# Dispositivo_H2O_Esquem_tico.net
KiCad netlist of a schematic drawn in EasyEDA
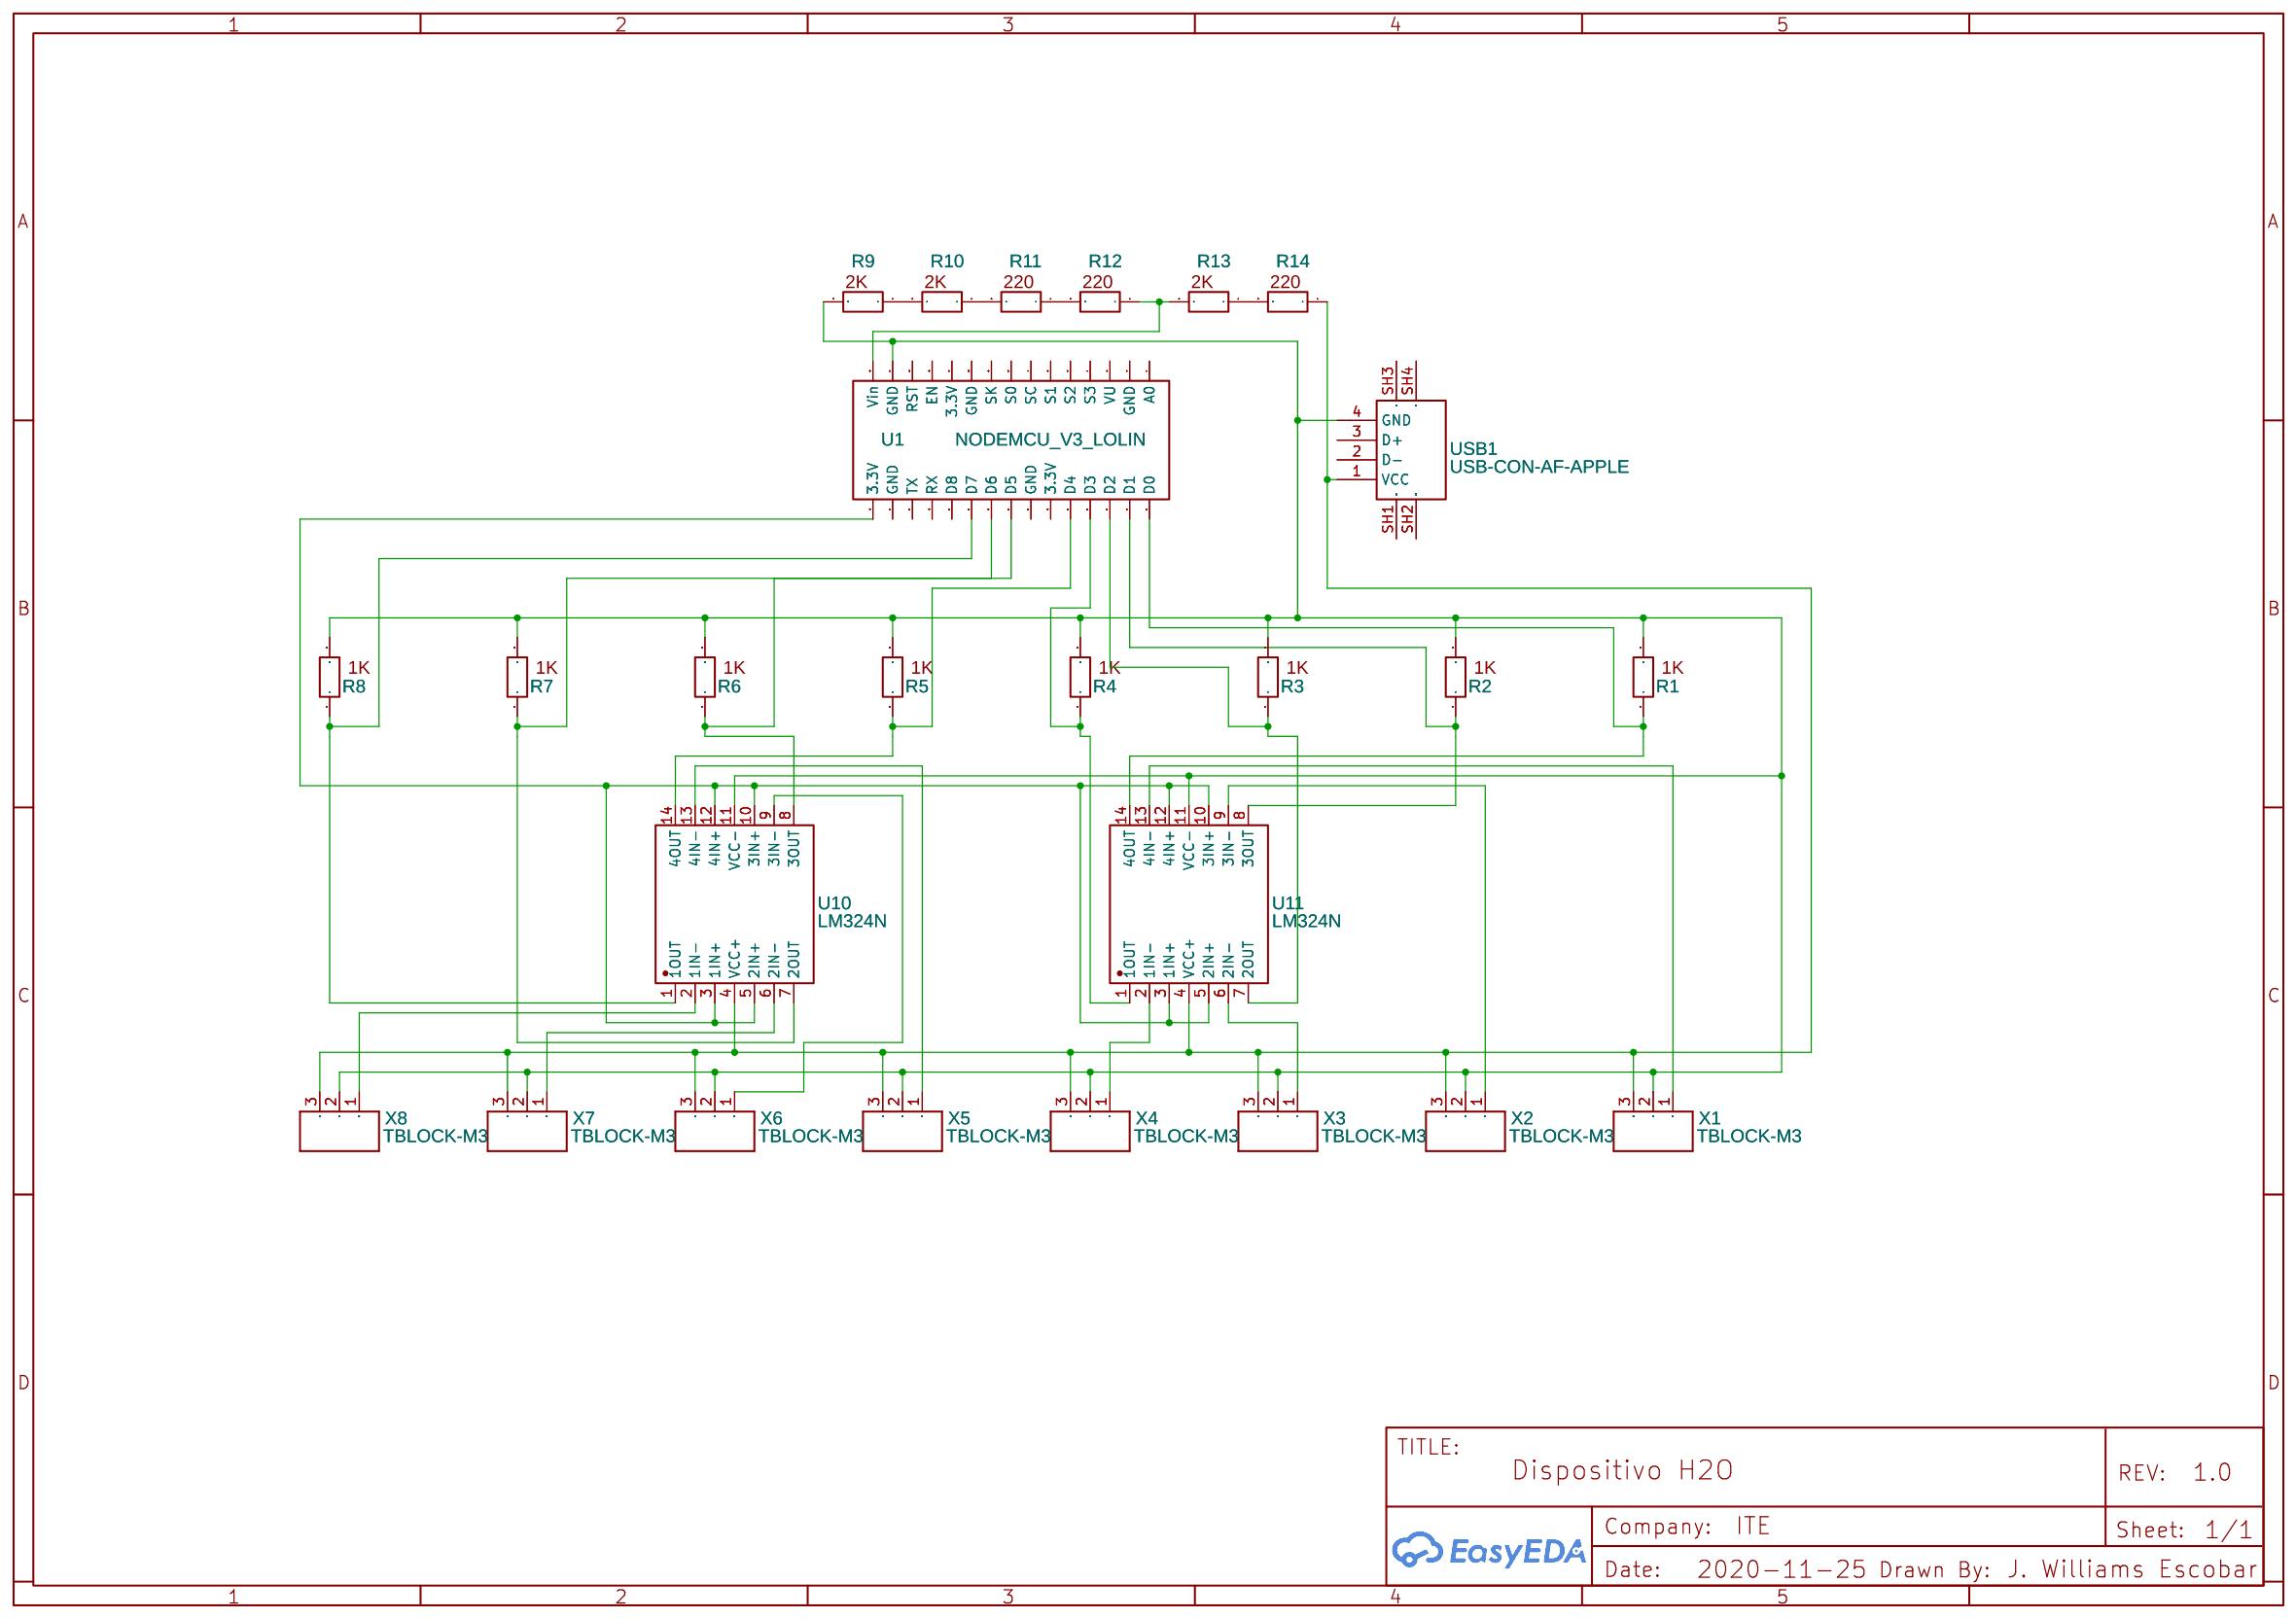
[diagram p0: schematic sheet]

(export (version "E")
  (design (tool "Eeschema 10.0.6"))
  (components
    (comp (ref "R1") (value "R9") (libsource (lib "") (part "Resistencia 1K_1")))
    (comp (ref "R2") (value "R9") (libsource (lib "") (part "Resistencia 1K_1")))
    (comp (ref "R3") (value "R9") (libsource (lib "") (part "Resistencia 1K_1")))
    (comp (ref "R4") (value "R9") (libsource (lib "") (part "Resistencia 1K_1")))
    (comp (ref "R5") (value "R9") (libsource (lib "") (part "Resistencia 1K_1")))
    (comp (ref "R6") (value "R9") (libsource (lib "") (part "Resistencia 1K_1")))
    (comp (ref "R7") (value "R9") (libsource (lib "") (part "Resistencia 1K_1")))
    (comp (ref "R8") (value "R9") (libsource (lib "") (part "Resistencia 1K_1")))
    (comp (ref "R9") (value "R9") (libsource (lib "") (part "Resistencia 1K_2")))
    (comp (ref "R10") (value "R16") (libsource (lib "") (part "Resistencia 1K_2")))
    (comp (ref "R11") (value "R17") (libsource (lib "") (part "Resistencia 1K")))
    (comp (ref "R12") (value "R9") (libsource (lib "") (part "Resistencia 1K")))
    (comp (ref "R13") (value "R9") (libsource (lib "") (part "Resistencia 1K_2")))
    (comp (ref "R14") (value "R9") (libsource (lib "") (part "Resistencia 1K")))
    (comp (ref "U1")
      (value "NODEMCU_V3_LOLIN")
      (fields (field (name "BOM_Manufacturer Part") "NodeMcu V3 LoLin"))
      (libsource (lib "") (part "NODEMCU_V3_LOLIN"))
    )
    (comp (ref "U10")
      (value "LM324N")
      (fields (field (name "BOM_Supplier Part") "C114380"))
      (libsource (lib "") (part "LM324N"))
    )
    (comp (ref "U11")
      (value "LM324N")
      (fields (field (name "BOM_Supplier Part") "C114380"))
      (libsource (lib "") (part "LM324N"))
    )
    (comp (ref "USB1")
      (value "USB-CON-AF-APPLE")
      (fields (field (name "BOM_Supplier Part") "C42567"))
      (libsource (lib "") (part "USB-CON-AF-APPLE"))
    )
    (comp (ref "X1") (value "TBLOCK-M3") (libsource (lib "") (part "TBLOCK-M3")))
    (comp (ref "X2") (value "TBLOCK-M3") (libsource (lib "") (part "TBLOCK-M3")))
    (comp (ref "X3") (value "TBLOCK-M3") (libsource (lib "") (part "TBLOCK-M3")))
    (comp (ref "X4") (value "TBLOCK-M3") (libsource (lib "") (part "TBLOCK-M3")))
    (comp (ref "X5") (value "TBLOCK-M3") (libsource (lib "") (part "TBLOCK-M3")))
    (comp (ref "X6") (value "TBLOCK-M3") (libsource (lib "") (part "TBLOCK-M3")))
    (comp (ref "X7") (value "TBLOCK-M3") (libsource (lib "") (part "TBLOCK-M3")))
    (comp (ref "X8") (value "TBLOCK-M3") (libsource (lib "") (part "TBLOCK-M3")))
  )
  (nets
    (net (code "1") (name "Net-(R10-Pad1)") (class "Default")
      (node (ref "R10") (pin "1") (pinfunction "1_1") (pintype "unspecified"))
      (node (ref "R11") (pin "2") (pinfunction "2_2") (pintype "unspecified"))
    )
    (net (code "2") (name "Net-(R10-Pad2)") (class "Default")
      (node (ref "R10") (pin "2") (pinfunction "2_2") (pintype "unspecified"))
      (node (ref "R9") (pin "1") (pinfunction "1_1") (pintype "unspecified"))
    )
    (net (code "3") (name "Net-(R11-Pad1)") (class "Default")
      (node (ref "R11") (pin "1") (pinfunction "1_1") (pintype "unspecified"))
      (node (ref "R12") (pin "2") (pinfunction "2_2") (pintype "unspecified"))
    )
    (net (code "4") (name "Net-(R13-Pad1)") (class "Default")
      (node (ref "R13") (pin "1") (pinfunction "1_1") (pintype "unspecified"))
      (node (ref "R14") (pin "2") (pinfunction "2_2") (pintype "unspecified"))
    )
    (net (code "5") (name "Net-(U1-D0)") (class "Default")
      (node (ref "R1") (pin "1") (pinfunction "1_1") (pintype "unspecified"))
      (node (ref "U1") (pin "30") (pinfunction "D0_30") (pintype "unspecified"))
      (node (ref "U11") (pin "14") (pinfunction "4OUT_14") (pintype "unspecified"))
    )
    (net (code "6") (name "Net-(U1-D1)") (class "Default")
      (node (ref "R2") (pin "1") (pinfunction "1_1") (pintype "unspecified"))
      (node (ref "U1") (pin "29") (pinfunction "D1_29") (pintype "unspecified"))
      (node (ref "U11") (pin "8") (pinfunction "3OUT_8") (pintype "unspecified"))
    )
    (net (code "7") (name "Net-(U1-D2)") (class "Default")
      (node (ref "R3") (pin "1") (pinfunction "1_1") (pintype "unspecified"))
      (node (ref "U1") (pin "28") (pinfunction "D2_28") (pintype "unspecified"))
      (node (ref "U11") (pin "7") (pinfunction "2OUT_7") (pintype "unspecified"))
    )
    (net (code "8") (name "Net-(U1-D3)") (class "Default")
      (node (ref "R4") (pin "1") (pinfunction "1_1") (pintype "unspecified"))
      (node (ref "U1") (pin "27") (pinfunction "D3_27") (pintype "unspecified"))
      (node (ref "U11") (pin "1") (pinfunction "1OUT_1") (pintype "unspecified"))
    )
    (net (code "9") (name "Net-(U1-D4)") (class "Default")
      (node (ref "R5") (pin "1") (pinfunction "1_1") (pintype "unspecified"))
      (node (ref "U1") (pin "26") (pinfunction "D4_26") (pintype "unspecified"))
      (node (ref "U10") (pin "14") (pinfunction "4OUT_14") (pintype "unspecified"))
    )
    (net (code "10") (name "Net-(U1-D5)") (class "Default")
      (node (ref "R6") (pin "1") (pinfunction "1_1") (pintype "unspecified"))
      (node (ref "U1") (pin "23") (pinfunction "D5_23") (pintype "unspecified"))
      (node (ref "U10") (pin "8") (pinfunction "3OUT_8") (pintype "unspecified"))
    )
    (net (code "11") (name "Net-(U1-D6)") (class "Default")
      (node (ref "R7") (pin "1") (pinfunction "1_1") (pintype "unspecified"))
      (node (ref "U1") (pin "22") (pinfunction "D6_22") (pintype "unspecified"))
      (node (ref "U10") (pin "7") (pinfunction "2OUT_7") (pintype "unspecified"))
    )
    (net (code "12") (name "Net-(U1-D7)") (class "Default")
      (node (ref "R8") (pin "1") (pinfunction "1_1") (pintype "unspecified"))
      (node (ref "U1") (pin "21") (pinfunction "D7_21") (pintype "unspecified"))
      (node (ref "U10") (pin "1") (pinfunction "1OUT_1") (pintype "unspecified"))
    )
    (net (code "13") (name "Net-(U1-Vin)") (class "Default")
      (node (ref "R12") (pin "1") (pinfunction "1_1") (pintype "unspecified"))
      (node (ref "R13") (pin "2") (pinfunction "2_2") (pintype "unspecified"))
      (node (ref "U1") (pin "15") (pinfunction "Vin_15") (pintype "unspecified"))
    )
    (net (code "14") (name "Net-(U10-1IN+)") (class "Default")
      (node (ref "U1") (pin "16") (pinfunction "3.3V_16") (pintype "unspecified"))
      (node (ref "U10") (pin "10") (pinfunction "3IN+_10") (pintype "unspecified"))
      (node (ref "U10") (pin "12") (pinfunction "4IN+_12") (pintype "unspecified"))
      (node (ref "U10") (pin "3") (pinfunction "1IN+_3") (pintype "unspecified"))
      (node (ref "U10") (pin "5") (pinfunction "2IN+_5") (pintype "unspecified"))
      (node (ref "U11") (pin "10") (pinfunction "3IN+_10") (pintype "unspecified"))
      (node (ref "U11") (pin "12") (pinfunction "4IN+_12") (pintype "unspecified"))
      (node (ref "U11") (pin "3") (pinfunction "1IN+_3") (pintype "unspecified"))
      (node (ref "U11") (pin "5") (pinfunction "2IN+_5") (pintype "unspecified"))
    )
    (net (code "15") (name "Net-(U10-1IN-)") (class "Default")
      (node (ref "U10") (pin "2") (pinfunction "1IN-_2") (pintype "unspecified"))
      (node (ref "X8") (pin "1") (pinfunction "P$1_1") (pintype "bidirectional"))
    )
    (net (code "16") (name "Net-(U10-2IN-)") (class "Default")
      (node (ref "U10") (pin "6") (pinfunction "2IN-_6") (pintype "unspecified"))
      (node (ref "X7") (pin "1") (pinfunction "P$1_1") (pintype "bidirectional"))
    )
    (net (code "17") (name "Net-(U10-3IN-)") (class "Default")
      (node (ref "U10") (pin "9") (pinfunction "3IN-_9") (pintype "unspecified"))
      (node (ref "X6") (pin "1") (pinfunction "P$1_1") (pintype "bidirectional"))
    )
    (net (code "18") (name "Net-(U10-4IN-)") (class "Default")
      (node (ref "U10") (pin "13") (pinfunction "4IN-_13") (pintype "unspecified"))
      (node (ref "X5") (pin "1") (pinfunction "P$1_1") (pintype "bidirectional"))
    )
    (net (code "19") (name "Net-(U10-VCC+)") (class "Default")
      (node (ref "R14") (pin "1") (pinfunction "1_1") (pintype "unspecified"))
      (node (ref "U10") (pin "4") (pinfunction "VCC+_4") (pintype "unspecified"))
      (node (ref "U11") (pin "4") (pinfunction "VCC+_4") (pintype "unspecified"))
      (node (ref "USB1") (pin "1") (pinfunction "VCC_1") (pintype "input"))
      (node (ref "X1") (pin "3") (pinfunction "P$3_3") (pintype "bidirectional"))
      (node (ref "X2") (pin "3") (pinfunction "P$3_3") (pintype "bidirectional"))
      (node (ref "X3") (pin "3") (pinfunction "P$3_3") (pintype "bidirectional"))
      (node (ref "X4") (pin "3") (pinfunction "P$3_3") (pintype "bidirectional"))
      (node (ref "X5") (pin "3") (pinfunction "P$3_3") (pintype "bidirectional"))
      (node (ref "X6") (pin "3") (pinfunction "P$3_3") (pintype "bidirectional"))
      (node (ref "X7") (pin "3") (pinfunction "P$3_3") (pintype "bidirectional"))
      (node (ref "X8") (pin "3") (pinfunction "P$3_3") (pintype "bidirectional"))
    )
    (net (code "20") (name "Net-(U10-VCC-)") (class "Default")
      (node (ref "R1") (pin "2") (pinfunction "2_2") (pintype "unspecified"))
      (node (ref "R2") (pin "2") (pinfunction "2_2") (pintype "unspecified"))
      (node (ref "R3") (pin "2") (pinfunction "2_2") (pintype "unspecified"))
      (node (ref "R4") (pin "2") (pinfunction "2_2") (pintype "unspecified"))
      (node (ref "R5") (pin "2") (pinfunction "2_2") (pintype "unspecified"))
      (node (ref "R6") (pin "2") (pinfunction "2_2") (pintype "unspecified"))
      (node (ref "R7") (pin "2") (pinfunction "2_2") (pintype "unspecified"))
      (node (ref "R8") (pin "2") (pinfunction "2_2") (pintype "unspecified"))
      (node (ref "R9") (pin "2") (pinfunction "2_2") (pintype "unspecified"))
      (node (ref "U1") (pin "14") (pinfunction "GND_14") (pintype "unspecified"))
      (node (ref "U10") (pin "11") (pinfunction "VCC-_11") (pintype "unspecified"))
      (node (ref "U11") (pin "11") (pinfunction "VCC-_11") (pintype "unspecified"))
      (node (ref "USB1") (pin "4") (pinfunction "GND_4") (pintype "input"))
      (node (ref "X1") (pin "2") (pinfunction "P$2_2") (pintype "bidirectional"))
      (node (ref "X2") (pin "2") (pinfunction "P$2_2") (pintype "bidirectional"))
      (node (ref "X3") (pin "2") (pinfunction "P$2_2") (pintype "bidirectional"))
      (node (ref "X4") (pin "2") (pinfunction "P$2_2") (pintype "bidirectional"))
      (node (ref "X5") (pin "2") (pinfunction "P$2_2") (pintype "bidirectional"))
      (node (ref "X6") (pin "2") (pinfunction "P$2_2") (pintype "bidirectional"))
      (node (ref "X7") (pin "2") (pinfunction "P$2_2") (pintype "bidirectional"))
      (node (ref "X8") (pin "2") (pinfunction "P$2_2") (pintype "bidirectional"))
    )
    (net (code "21") (name "Net-(U11-1IN-)") (class "Default")
      (node (ref "U11") (pin "2") (pinfunction "1IN-_2") (pintype "unspecified"))
      (node (ref "X4") (pin "1") (pinfunction "P$1_1") (pintype "bidirectional"))
    )
    (net (code "22") (name "Net-(U11-2IN-)") (class "Default")
      (node (ref "U11") (pin "6") (pinfunction "2IN-_6") (pintype "unspecified"))
      (node (ref "X3") (pin "1") (pinfunction "P$1_1") (pintype "bidirectional"))
    )
    (net (code "23") (name "Net-(U11-3IN-)") (class "Default")
      (node (ref "U11") (pin "9") (pinfunction "3IN-_9") (pintype "unspecified"))
      (node (ref "X2") (pin "1") (pinfunction "P$1_1") (pintype "bidirectional"))
    )
    (net (code "24") (name "Net-(U11-4IN-)") (class "Default")
      (node (ref "U11") (pin "13") (pinfunction "4IN-_13") (pintype "unspecified"))
      (node (ref "X1") (pin "1") (pinfunction "P$1_1") (pintype "bidirectional"))
    )
    (net (code "25") (name "unconnected-(U1-3.3V-Pad11)") (class "Default")
      (node (ref "U1") (pin "11") (pinfunction "3.3V_11") (pintype "unspecified"))
    )
    (net (code "26") (name "unconnected-(U1-3.3V-Pad25)") (class "Default")
      (node (ref "U1") (pin "25") (pinfunction "3.3V_25") (pintype "unspecified"))
    )
    (net (code "27") (name "unconnected-(U1-A0-Pad1)") (class "Default")
      (node (ref "U1") (pin "1") (pinfunction "A0_1") (pintype "unspecified"))
    )
    (net (code "28") (name "unconnected-(U1-D8-Pad20)") (class "Default")
      (node (ref "U1") (pin "20") (pinfunction "D8_20") (pintype "unspecified"))
    )
    (net (code "29") (name "unconnected-(U1-EN-Pad12)") (class "Default")
      (node (ref "U1") (pin "12") (pinfunction "EN_12") (pintype "unspecified"))
    )
    (net (code "30") (name "unconnected-(U1-GND-Pad2)") (class "Default")
      (node (ref "U1") (pin "2") (pinfunction "GND_2") (pintype "unspecified"))
    )
    (net (code "31") (name "unconnected-(U1-GND-Pad10)") (class "Default")
      (node (ref "U1") (pin "10") (pinfunction "GND_10") (pintype "unspecified"))
    )
    (net (code "32") (name "unconnected-(U1-GND-Pad17)") (class "Default")
      (node (ref "U1") (pin "17") (pinfunction "GND_17") (pintype "unspecified"))
    )
    (net (code "33") (name "unconnected-(U1-GND-Pad24)") (class "Default")
      (node (ref "U1") (pin "24") (pinfunction "GND_24") (pintype "unspecified"))
    )
    (net (code "34") (name "unconnected-(U1-RST-Pad13)") (class "Default")
      (node (ref "U1") (pin "13") (pinfunction "RST_13") (pintype "unspecified"))
    )
    (net (code "35") (name "unconnected-(U1-RX-Pad19)") (class "Default")
      (node (ref "U1") (pin "19") (pinfunction "RX_19") (pintype "unspecified"))
    )
    (net (code "36") (name "unconnected-(U1-S0-Pad8)") (class "Default")
      (node (ref "U1") (pin "8") (pinfunction "S0_8") (pintype "unspecified"))
    )
    (net (code "37") (name "unconnected-(U1-S1-Pad6)") (class "Default")
      (node (ref "U1") (pin "6") (pinfunction "S1_6") (pintype "unspecified"))
    )
    (net (code "38") (name "unconnected-(U1-S2-Pad5)") (class "Default")
      (node (ref "U1") (pin "5") (pinfunction "S2_5") (pintype "unspecified"))
    )
    (net (code "39") (name "unconnected-(U1-S3-Pad4)") (class "Default")
      (node (ref "U1") (pin "4") (pinfunction "S3_4") (pintype "unspecified"))
    )
    (net (code "40") (name "unconnected-(U1-SC-Pad7)") (class "Default")
      (node (ref "U1") (pin "7") (pinfunction "SC_7") (pintype "unspecified"))
    )
    (net (code "41") (name "unconnected-(U1-SK-Pad9)") (class "Default")
      (node (ref "U1") (pin "9") (pinfunction "SK_9") (pintype "unspecified"))
    )
    (net (code "42") (name "unconnected-(U1-TX-Pad18)") (class "Default")
      (node (ref "U1") (pin "18") (pinfunction "TX_18") (pintype "unspecified"))
    )
    (net (code "43") (name "unconnected-(U1-VU-Pad3)") (class "Default")
      (node (ref "U1") (pin "3") (pinfunction "VU_3") (pintype "unspecified"))
    )
    (net (code "44") (name "unconnected-(USB1-D+-Pad3)") (class "Default")
      (node (ref "USB1") (pin "3") (pinfunction "D+_3") (pintype "input"))
    )
    (net (code "45") (name "unconnected-(USB1-D--Pad2)") (class "Default")
      (node (ref "USB1") (pin "2") (pinfunction "D-_2") (pintype "input"))
    )
    (net (code "46") (name "unconnected-(USB1-PadSH1)") (class "Default")
      (node (ref "USB1") (pin "SH1") (pinfunction "SH1_SH1") (pintype "unspecified"))
    )
    (net (code "47") (name "unconnected-(USB1-PadSH2)") (class "Default")
      (node (ref "USB1") (pin "SH2") (pinfunction "SH2_SH2") (pintype "unspecified"))
    )
    (net (code "48") (name "unconnected-(USB1-PadSH3)") (class "Default")
      (node (ref "USB1") (pin "SH3") (pinfunction "SH3_SH3") (pintype "unspecified"))
    )
    (net (code "49") (name "unconnected-(USB1-PadSH4)") (class "Default")
      (node (ref "USB1") (pin "SH4") (pinfunction "SH4_SH4") (pintype "unspecified"))
    )
  )
)
